# breadboard_usb.net
KiCad netlist of a schematic drawn in EAGLE
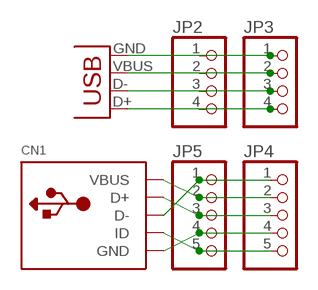
[diagram p0: schematic, sheet 1]

(export (version "E")
  (design (tool "Eeschema 10.0.6"))
  (components
    (comp (ref "CN1")
      (value "USBTHM")
      (footprint "eagle-import:USB-MINIB-THM")
      (libsource (lib "eagle-import") (part "USBTHM"))
    )
    (comp (ref "JP1")
      (value "USB-B")
      (footprint "eagle-import:USB-B-PTH")
      (libsource (lib "eagle-import") (part "USBPTH"))
    )
    (comp (ref "JP2")
      (value "PINHD-1X4")
      (footprint "eagle-import:1X04")
      (libsource (lib "eagle-import") (part "PINHD-1X4"))
    )
    (comp (ref "JP3")
      (value "PINHD-1X4")
      (footprint "eagle-import:1X04")
      (libsource (lib "eagle-import") (part "PINHD-1X4"))
    )
    (comp (ref "JP4")
      (value "PINHD-1X5")
      (footprint "eagle-import:1X05")
      (libsource (lib "eagle-import") (part "PINHD-1X5"))
    )
    (comp (ref "JP5")
      (value "PINHD-1X5")
      (footprint "eagle-import:1X05")
      (libsource (lib "eagle-import") (part "PINHD-1X5"))
    )
  )
  (nets
    (net (code "1") (name "Net-(CN1-PadD+)") (class "Default")
      (node (ref "CN1") (pin "D+") (pinfunction "D+_D+") (pintype "bidirectional"))
      (node (ref "JP4") (pin "3") (pinfunction "3_3") (pintype "passive"))
      (node (ref "JP5") (pin "3") (pinfunction "3_3") (pintype "passive"))
    )
    (net (code "2") (name "Net-(CN1-PadD-)") (class "Default")
      (node (ref "CN1") (pin "D-") (pinfunction "D-_D-") (pintype "bidirectional"))
      (node (ref "JP4") (pin "1") (pinfunction "1_1") (pintype "passive"))
      (node (ref "JP5") (pin "1") (pinfunction "1_1") (pintype "passive"))
    )
    (net (code "3") (name "Net-(CN1-PadGND)") (class "Default")
      (node (ref "CN1") (pin "GND") (pinfunction "GND_GND") (pintype "power_in"))
      (node (ref "JP4") (pin "4") (pinfunction "4_4") (pintype "passive"))
      (node (ref "JP5") (pin "4") (pinfunction "4_4") (pintype "passive"))
    )
    (net (code "4") (name "Net-(CN1-PadID)") (class "Default")
      (node (ref "CN1") (pin "ID") (pinfunction "ID_ID") (pintype "bidirectional"))
      (node (ref "JP4") (pin "5") (pinfunction "5_5") (pintype "passive"))
      (node (ref "JP5") (pin "5") (pinfunction "5_5") (pintype "passive"))
    )
    (net (code "5") (name "Net-(CN1-PadVBUS)") (class "Default")
      (node (ref "CN1") (pin "VBUS") (pinfunction "VBUS_VBUS") (pintype "power_in"))
      (node (ref "JP4") (pin "2") (pinfunction "2_2") (pintype "passive"))
      (node (ref "JP5") (pin "2") (pinfunction "2_2") (pintype "passive"))
    )
    (net (code "6") (name "Net-(JP1-PadD+)") (class "Default")
      (node (ref "JP1") (pin "D+") (pinfunction "D+_D+") (pintype "bidirectional"))
      (node (ref "JP2") (pin "4") (pinfunction "4_4") (pintype "passive"))
      (node (ref "JP3") (pin "4") (pinfunction "4_4") (pintype "passive"))
    )
    (net (code "7") (name "Net-(JP1-PadD-)") (class "Default")
      (node (ref "JP1") (pin "D-") (pinfunction "D-_D-") (pintype "bidirectional"))
      (node (ref "JP2") (pin "3") (pinfunction "3_3") (pintype "passive"))
      (node (ref "JP3") (pin "3") (pinfunction "3_3") (pintype "passive"))
    )
    (net (code "8") (name "Net-(JP1-PadGND)") (class "Default")
      (node (ref "JP1") (pin "GND") (pinfunction "GND_GND") (pintype "bidirectional"))
      (node (ref "JP2") (pin "1") (pinfunction "1_1") (pintype "passive"))
      (node (ref "JP3") (pin "1") (pinfunction "1_1") (pintype "passive"))
    )
    (net (code "9") (name "Net-(JP1-PadVBUS)") (class "Default")
      (node (ref "JP1") (pin "VBUS") (pinfunction "VBUS_VBUS") (pintype "bidirectional"))
      (node (ref "JP2") (pin "2") (pinfunction "2_2") (pintype "passive"))
      (node (ref "JP3") (pin "2") (pinfunction "2_2") (pintype "passive"))
    )
  )
)
